# Power.net
KiCad netlist of a schematic drawn in Altium Designer
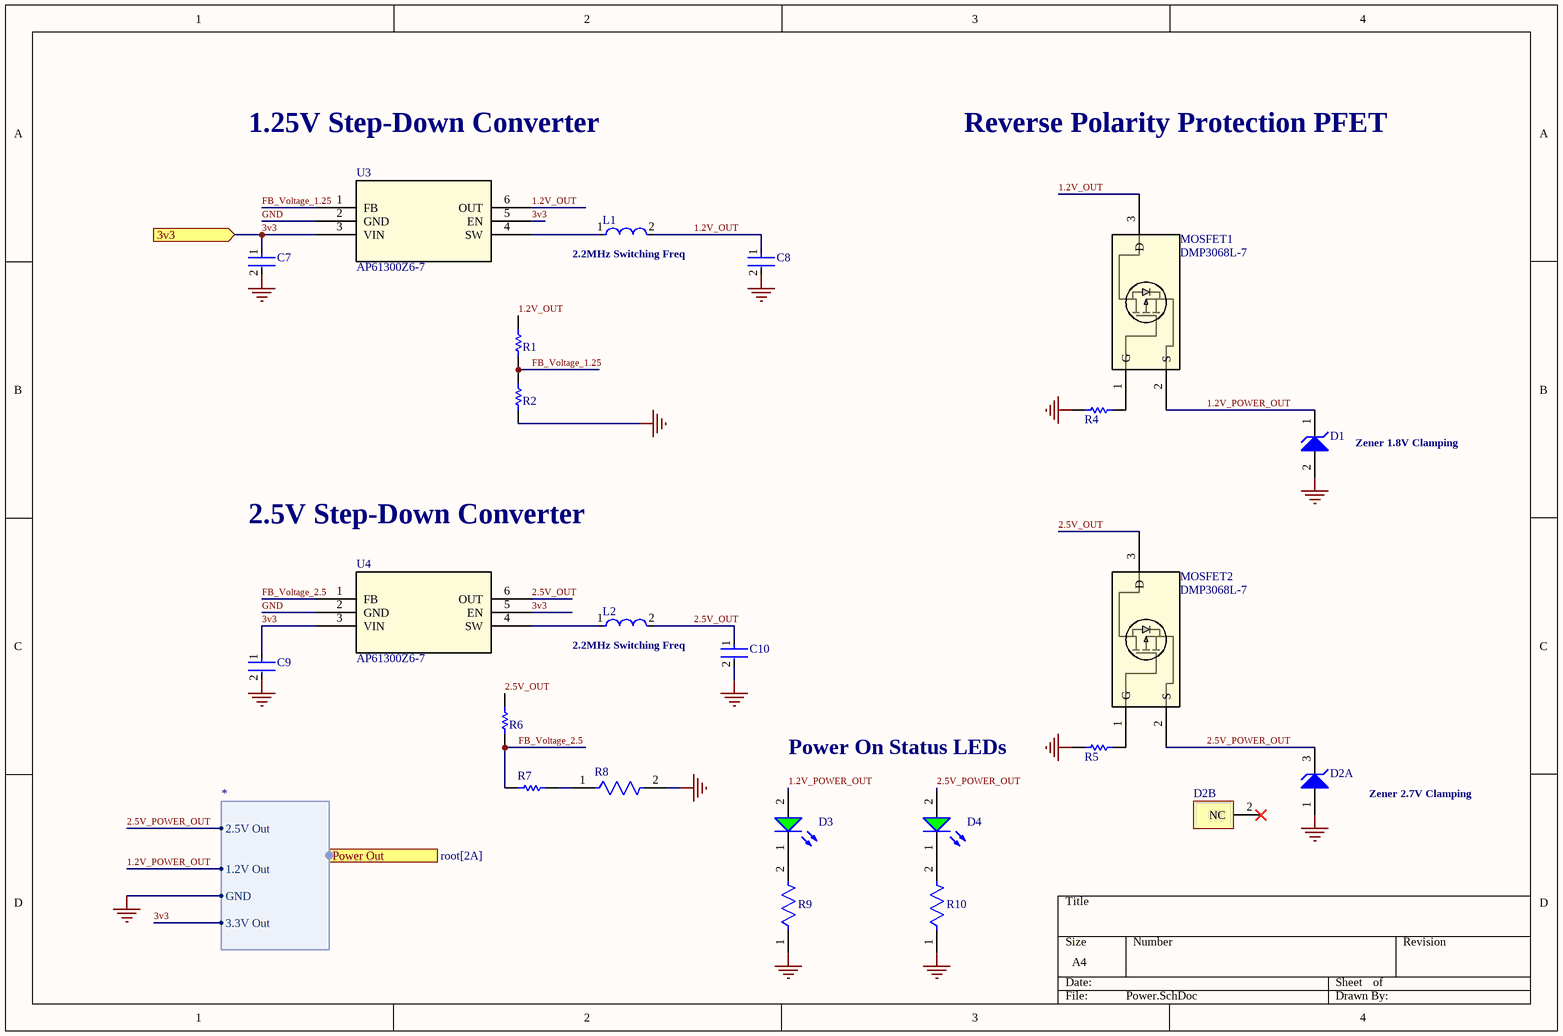
[diagram p0: Power.SchDoc]

(export (version "E")
  (design (tool "Eeschema 10.0.6"))
  (components
    (comp (ref "C7")
      (value "GRT21BR61E226ME13L")
      (footprint "FP-GRT21B-0_2-IPC_C")
      (description "Multi-Layer Ceramic Capacitor 22uF 25V X5R ±20% 0805 Emboss T/R")
      (fields (field (name "TOLERANCE") "20%"))
      (libsource (lib "Altium Content Vault") (part "02cd4be3c70576c341d710602a673aa"))
    )
    (comp (ref "C8")
      (value "GRT21BR61E226ME13L")
      (footprint "FP-GRT21B-0_2-IPC_C")
      (description "Multi-Layer Ceramic Capacitor 22uF 25V X5R ±20% 0805 Emboss T/R")
      (fields (field (name "TOLERANCE") "20%"))
      (libsource (lib "Altium Content Vault") (part "02cd4be3c70576c341d710602a673aa"))
    )
    (comp (ref "C9")
      (value "GRT21BR61E226ME13L")
      (footprint "FP-GRT21B-0_2-IPC_C")
      (description "Multi-Layer Ceramic Capacitor 22uF 25V X5R ±20% 0805 Emboss T/R")
      (fields (field (name "TOLERANCE") "20%"))
      (libsource (lib "Altium Content Vault") (part "02cd4be3c70576c341d710602a673aa"))
    )
    (comp (ref "C10")
      (value "GRT21BR61E226ME13L")
      (footprint "FP-GRT21B-0_2-IPC_C")
      (description "Multi-Layer Ceramic Capacitor 22uF 25V X5R ±20% 0805 Emboss T/R")
      (fields (field (name "TOLERANCE") "20%"))
      (libsource (lib "Altium Content Vault") (part "02cd4be3c70576c341d710602a673aa"))
    )
    (comp (ref "D1")
      (value "SZMMSZ4678T1G")
      (footprint "ONSC-SOD-123-2-425-04_V")
      (description "Zener Voltage Regulator, 500 mW, 2-Pin SOD-123, Pb-Free, Tape and Reel")
      (fields (field (name "MANUFACTURER") "On Semiconductor"))
      (libsource (lib "Altium Content Vault") (part "ONSC-K1A2-2"))
    )
    (comp (ref "D2")
      (value "MMBZ5223BLT1G")
      (footprint "ONSC-SOT-23-3-318-08_V")
      (description "Zener Voltage Regulator, 225 mW, 3-Pin SOT-23, Pb-Free, Tape and Reel")
      (fields (field (name "MANUFACTURER") "On Semiconductor"))
      (libsource (lib "Altium Content Vault") (part "ONSC-A1K3-3"))
    )
    (comp (ref "D3")
      (value "150060VS75000")
      (footprint "WL-SMCW_0603_150060xx75000")
      (description "WURTH ELEKTRONIK - 150060VS75000 - LED, Green, SMD, 0603, 30 mA, 2 V, 570 nm")
      (libsource (lib "Altium Content Vault") (part "LED_Green_2A-1K"))
    )
    (comp (ref "D4")
      (value "150060VS75000")
      (footprint "WL-SMCW_0603_150060xx75000")
      (description "WURTH ELEKTRONIK - 150060VS75000 - LED, Green, SMD, 0603, 30 mA, 2 V, 570 nm")
      (libsource (lib "Altium Content Vault") (part "LED_Green_2A-1K"))
    )
    (comp (ref "L1")
      (value "MLP2012H2R2MT0S1")
      (footprint "FP-MLP2012M-IPC_C")
      (description "Shielded Multilayer Inductor 2.2uH ±20% 1000mA 195mΩ SMD 0805")
      (fields (field (name "TOLERANCE") "20%"))
      (libsource (lib "Altium Content Vault") (part "725321dda6339637d4d059423bc1c3c"))
    )
    (comp (ref "L2")
      (value "MLP2012H2R2MT0S1")
      (footprint "FP-MLP2012M-IPC_C")
      (description "Shielded Multilayer Inductor 2.2uH ±20% 1000mA 195mΩ SMD 0805")
      (fields (field (name "TOLERANCE") "20%"))
      (libsource (lib "Altium Content Vault") (part "725321dda6339637d4d059423bc1c3c"))
    )
    (comp (ref "MOSFET1")
      (value "DMP3068L-7")
      (footprint "SOT-23_DMP3068L_DIO")
      (description "No Description Available")
      (fields (field (name "COPYRIGHT") "Copyright (C) 2025 Ultra Librarian. All rights reserved."))
      (libsource (lib "DMP3068L-7") (part "DMP3068L-7"))
    )
    (comp (ref "MOSFET2")
      (value "DMP3068L-7")
      (footprint "SOT-23_DMP3068L_DIO")
      (description "No Description Available")
      (fields (field (name "COPYRIGHT") "Copyright (C) 2025 Ultra Librarian. All rights reserved."))
      (libsource (lib "DMP3068L-7") (part "DMP3068L-7"))
    )
    (comp (ref "R1")
      (value "ERJ-2RKF2003X")
      (footprint "RESC1005X40X25NL05T05")
      (description "Chip Resistor, 200 KOhm, +/- 1%, 100 mW, -55 to 155 degC, 0402 (1005 Metric), RoHS, Tape and Reel")
      (fields (field (name "TOLERANCE") "1%") (field (name "MANUFACTURER") "Basic Passives"))
      (libsource (lib "Altium Content Vault") (part "RES-2"))
    )
    (comp (ref "R2")
      (value "RC0402FR-07100KL")
      (footprint "RESC1005X40X25NL05T10")
      (fields (field (name "MANUFACTURER") "Yageo / Phycomp"))
      (libsource (lib "Altium Content Vault") (part "RES"))
    )
    (comp (ref "R4")
      (value "RC0402FR-07100KL")
      (footprint "RESC1005X40X25NL05T10")
      (fields (field (name "MANUFACTURER") "Yageo / Phycomp"))
      (libsource (lib "Altium Content Vault") (part "RES"))
    )
    (comp (ref "R5")
      (value "RC0402FR-07100KL")
      (footprint "RESC1005X40X25NL05T10")
      (fields (field (name "MANUFACTURER") "Yageo / Phycomp"))
      (libsource (lib "Altium Content Vault") (part "RES"))
    )
    (comp (ref "R6")
      (value "ERJ-2RKF2003X")
      (footprint "RESC1005X40X25NL05T05")
      (description "Chip Resistor, 200 KOhm, +/- 1%, 100 mW, -55 to 155 degC, 0402 (1005 Metric), RoHS, Tape and Reel")
      (fields (field (name "TOLERANCE") "1%") (field (name "MANUFACTURER") "Basic Passives"))
      (libsource (lib "Altium Content Vault") (part "RES-2"))
    )
    (comp (ref "R7")
      (value "RC0402FR-0744K2L")
      (footprint "RESC1005X40X25NL05T10")
      (fields (field (name "MANUFACTURER") "Yageo / Phycomp"))
      (libsource (lib "Altium Content Vault") (part "RES"))
    )
    (comp (ref "R8")
      (value "RC0402FR-0720KL")
      (footprint "FP-RC0402-0_4-MFG")
      (fields (field (name "TOLERANCE") "1%"))
      (libsource (lib "Altium Content Vault") (part "1029c3af85768c4190bb7ad29bc67b5"))
    )
    (comp (ref "R9")
      (value "RC0603FR-0710KL")
      (footprint "FP-RC0603-0_55-IPC_C")
      (description "RES 10K OHM 1% 1/10W 0603")
      (fields (field (name "TOLERANCE") "1%"))
      (libsource (lib "Altium Content Vault") (part "1029c3af85768c4190bb7ad29bc67b5"))
    )
    (comp (ref "R10")
      (value "RC0603FR-0710KL")
      (footprint "FP-RC0603-0_55-IPC_C")
      (description "RES 10K OHM 1% 1/10W 0603")
      (fields (field (name "TOLERANCE") "1%"))
      (libsource (lib "Altium Content Vault") (part "1029c3af85768c4190bb7ad29bc67b5"))
    )
    (comp (ref "U3")
      (value "AP61300Z6-7")
      (footprint "AP61300Z6-7_DIO")
      (description "No Description Available")
      (fields (field (name "COPYRIGHT") "Copyright (C) 2025 Ultra Librarian. All rights reserved."))
      (libsource (lib "AP61300Z6-7") (part "AP61300Z6-7"))
    )
    (comp (ref "U4")
      (value "AP61300Z6-7")
      (footprint "AP61300Z6-7_DIO")
      (description "No Description Available")
      (fields (field (name "COPYRIGHT") "Copyright (C) 2025 Ultra Librarian. All rights reserved."))
      (libsource (lib "AP61300Z6-7") (part "AP61300Z6-7"))
    )
  )
  (nets
    (net (code "2") (name "/1.2V_OUT") (class "Default")
      (node (ref "C8") (pin "1") (pinfunction "1_1") (pintype "passive"))
      (node (ref "L1") (pin "2") (pinfunction "2_2") (pintype "passive"))
      (node (ref "MOSFET1") (pin "3") (pinfunction "D_3") (pintype "passive"))
      (node (ref "R1") (pin "1") (pinfunction "1_1") (pintype "passive"))
      (node (ref "U3") (pin "6") (pinfunction "OUT_6") (pintype "passive"))
    )
    (net (code "3") (name "/1.2V_POWER_OUT") (class "Default")
      (node (ref "D1") (pin "1") (pinfunction "K_1") (pintype "passive"))
      (node (ref "D3") (pin "2") (pinfunction "A_2") (pintype "passive"))
      (node (ref "MOSFET1") (pin "2") (pinfunction "S_2") (pintype "passive"))
    )
    (net (code "4") (name "/2.5V_OUT") (class "Default")
      (node (ref "C10") (pin "1") (pinfunction "1_1") (pintype "passive"))
      (node (ref "L2") (pin "2") (pinfunction "2_2") (pintype "passive"))
      (node (ref "MOSFET2") (pin "3") (pinfunction "D_3") (pintype "passive"))
      (node (ref "R6") (pin "1") (pinfunction "1_1") (pintype "passive"))
      (node (ref "U4") (pin "6") (pinfunction "OUT_6") (pintype "passive"))
    )
    (net (code "5") (name "/2.5V_POWER_OUT") (class "Default")
      (node (ref "D2") (pin "3") (pinfunction "K_3") (pintype "passive"))
      (node (ref "D4") (pin "2") (pinfunction "A_2") (pintype "passive"))
      (node (ref "MOSFET2") (pin "2") (pinfunction "S_2") (pintype "passive"))
    )
    (net (code "6") (name "/3v3") (class "Default")
      (node (ref "C7") (pin "1") (pinfunction "1_1") (pintype "passive"))
      (node (ref "C9") (pin "1") (pinfunction "1_1") (pintype "passive"))
      (node (ref "U3") (pin "3") (pinfunction "VIN_3") (pintype "passive"))
      (node (ref "U3") (pin "5") (pinfunction "EN_5") (pintype "passive"))
      (node (ref "U4") (pin "3") (pinfunction "VIN_3") (pintype "passive"))
      (node (ref "U4") (pin "5") (pinfunction "EN_5") (pintype "passive"))
    )
    (net (code "7") (name "/FB_Voltage_1.25") (class "Default")
      (node (ref "R1") (pin "2") (pinfunction "2_2") (pintype "passive"))
      (node (ref "R2") (pin "1") (pinfunction "1_1") (pintype "passive"))
      (node (ref "U3") (pin "1") (pinfunction "FB_1") (pintype "passive"))
    )
    (net (code "8") (name "/FB_Voltage_2.5") (class "Default")
      (node (ref "R6") (pin "2") (pinfunction "2_2") (pintype "passive"))
      (node (ref "R7") (pin "1") (pinfunction "1_1") (pintype "passive"))
      (node (ref "U4") (pin "1") (pinfunction "FB_1") (pintype "passive"))
    )
    (net (code "10") (name "GND") (class "Default")
      (node (ref "C10") (pin "2") (pinfunction "2_2") (pintype "passive"))
      (node (ref "C7") (pin "2") (pinfunction "2_2") (pintype "passive"))
      (node (ref "C8") (pin "2") (pinfunction "2_2") (pintype "passive"))
      (node (ref "C9") (pin "2") (pinfunction "2_2") (pintype "passive"))
      (node (ref "D1") (pin "2") (pinfunction "A_2") (pintype "passive"))
      (node (ref "D2") (pin "1") (pinfunction "A_1") (pintype "passive"))
      (node (ref "R10") (pin "1") (pinfunction "1_1") (pintype "passive"))
      (node (ref "R2") (pin "2") (pinfunction "2_2") (pintype "passive"))
      (node (ref "R4") (pin "2") (pinfunction "2_2") (pintype "passive"))
      (node (ref "R5") (pin "2") (pinfunction "2_2") (pintype "passive"))
      (node (ref "R8") (pin "2") (pinfunction "2_2") (pintype "passive"))
      (node (ref "R9") (pin "1") (pinfunction "1_1") (pintype "passive"))
      (node (ref "U3") (pin "2") (pinfunction "GND_2") (pintype "passive"))
      (node (ref "U4") (pin "2") (pinfunction "GND_2") (pintype "passive"))
    )
    (net (code "11") (name "Net-(D3-K)") (class "Default")
      (node (ref "D3") (pin "1") (pinfunction "K_1") (pintype "passive"))
      (node (ref "R9") (pin "2") (pinfunction "2_2") (pintype "passive"))
    )
    (net (code "12") (name "Net-(D4-K)") (class "Default")
      (node (ref "D4") (pin "1") (pinfunction "K_1") (pintype "passive"))
      (node (ref "R10") (pin "2") (pinfunction "2_2") (pintype "passive"))
    )
    (net (code "13") (name "Net-(MOSFET1-G)") (class "Default")
      (node (ref "MOSFET1") (pin "1") (pinfunction "G_1") (pintype "passive"))
      (node (ref "R4") (pin "1") (pinfunction "1_1") (pintype "passive"))
    )
    (net (code "14") (name "Net-(MOSFET2-G)") (class "Default")
      (node (ref "MOSFET2") (pin "1") (pinfunction "G_1") (pintype "passive"))
      (node (ref "R5") (pin "1") (pinfunction "1_1") (pintype "passive"))
    )
    (net (code "15") (name "Net-(R7-Pad2)") (class "Default")
      (node (ref "R7") (pin "2") (pinfunction "2_2") (pintype "passive"))
      (node (ref "R8") (pin "1") (pinfunction "1_1") (pintype "passive"))
    )
    (net (code "16") (name "Net-(U3-SW)") (class "Default")
      (node (ref "L1") (pin "1") (pinfunction "1_1") (pintype "passive"))
      (node (ref "U3") (pin "4") (pinfunction "SW_4") (pintype "passive"))
    )
    (net (code "17") (name "Net-(U4-SW)") (class "Default")
      (node (ref "L2") (pin "1") (pinfunction "1_1") (pintype "passive"))
      (node (ref "U4") (pin "4") (pinfunction "SW_4") (pintype "passive"))
    )
    (net (code "18") (name "unconnected-(D2B-NC-Pad2)") (class "Default")
      (node (ref "D2") (pin "2") (pinfunction "NC_2") (pintype "passive+no_connect"))
    )
  )
)
